# rpi-hxb-shield.net
KiCad netlist of a schematic drawn in EAGLE
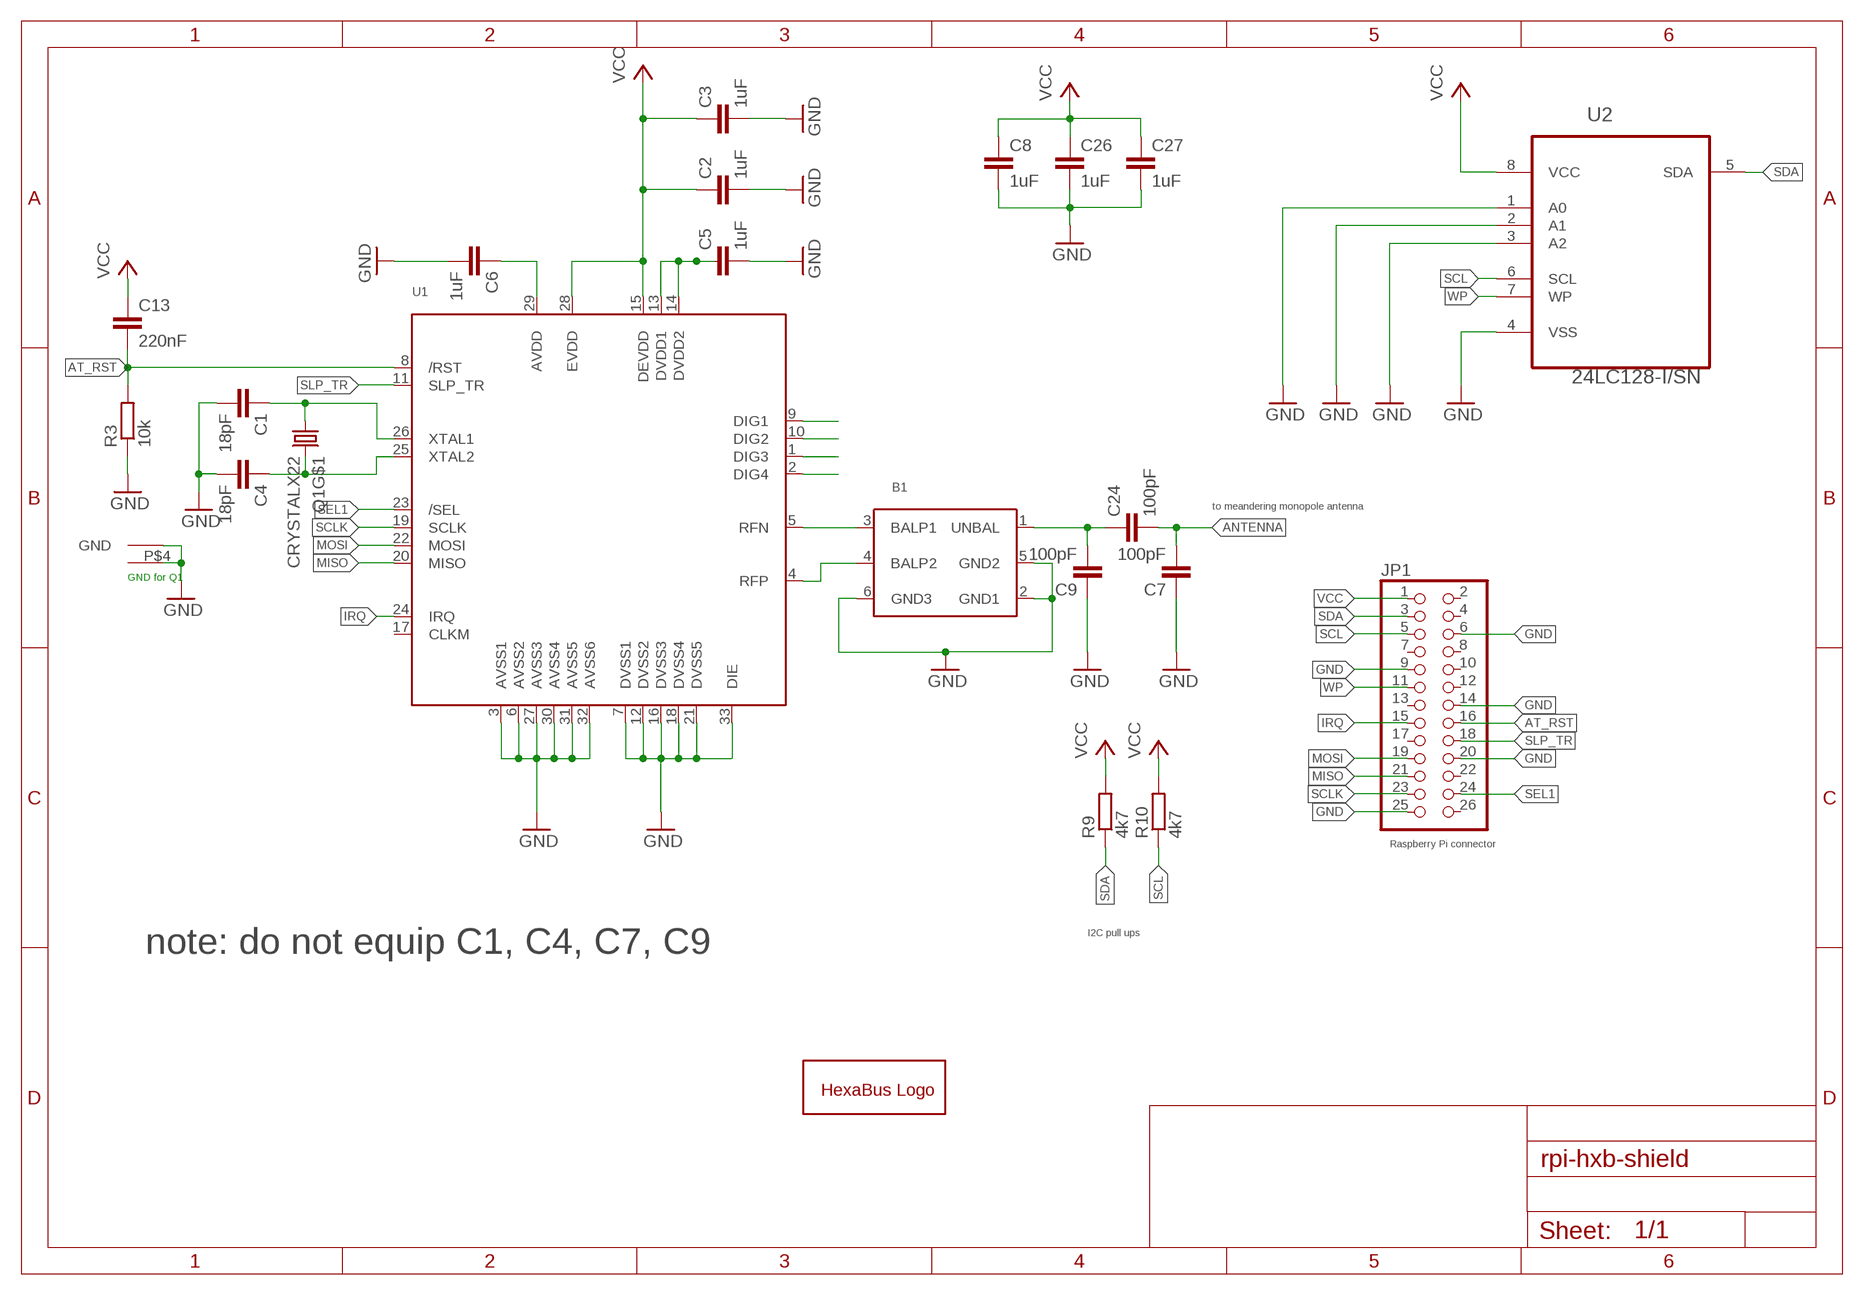
[diagram p0: schematic, sheet 1]

(export (version "E")
  (design (tool "Eeschema 10.0.6"))
  (components
    (comp (ref "B1")
      (value "BALUN+LP")
      (footprint "eagle-import:BALUN0805")
      (libsource (lib "eagle-import") (part "BALUN+LP"))
    )
    (comp (ref "C1")
      (value "18pF")
      (footprint "eagle-import:C0402K")
      (libsource (lib "eagle-import") (part "C-EUC0402K"))
    )
    (comp (ref "C2")
      (value "1uF")
      (footprint "eagle-import:C0402K")
      (libsource (lib "eagle-import") (part "C-EUC0402K"))
    )
    (comp (ref "C3")
      (value "1uF")
      (footprint "eagle-import:C0402K")
      (libsource (lib "eagle-import") (part "C-EUC0402K"))
    )
    (comp (ref "C4")
      (value "18pF")
      (footprint "eagle-import:C0402K")
      (libsource (lib "eagle-import") (part "C-EUC0402K"))
    )
    (comp (ref "C5")
      (value "1uF")
      (footprint "eagle-import:C0402K")
      (libsource (lib "eagle-import") (part "C-EUC0402K"))
    )
    (comp (ref "C6")
      (value "1uF")
      (footprint "eagle-import:C0402K")
      (libsource (lib "eagle-import") (part "C-EUC0402K"))
    )
    (comp (ref "C7")
      (value "100pF")
      (footprint "eagle-import:C0402K")
      (libsource (lib "eagle-import") (part "C-EUC0402K"))
    )
    (comp (ref "C8")
      (value "1uF")
      (footprint "eagle-import:C0402K")
      (libsource (lib "eagle-import") (part "C-EUC0402K"))
    )
    (comp (ref "C9")
      (value "100pF")
      (footprint "eagle-import:C0402K")
      (libsource (lib "eagle-import") (part "C-EUC0402K"))
    )
    (comp (ref "C13")
      (value "220nF")
      (footprint "eagle-import:C0402K")
      (libsource (lib "eagle-import") (part "C-EUC0402K"))
    )
    (comp (ref "C24")
      (value "100pF")
      (footprint "eagle-import:C0402K")
      (libsource (lib "eagle-import") (part "C-EUC0402K"))
    )
    (comp (ref "C26")
      (value "1uF")
      (footprint "eagle-import:C0402K")
      (libsource (lib "eagle-import") (part "C-EUC0402K"))
    )
    (comp (ref "C27")
      (value "1uF")
      (footprint "eagle-import:C0402K")
      (libsource (lib "eagle-import") (part "C-EUC0402K"))
    )
    (comp (ref "JP1")
      (value "PINHD-2X13")
      (footprint "eagle-import:2X13")
      (libsource (lib "eagle-import") (part "PINHD-2X13"))
    )
    (comp (ref "Q1")
      (value "CRYSTALX22")
      (footprint "eagle-import:X22")
      (libsource (lib "eagle-import") (part "CRYSTALX22"))
    )
    (comp (ref "R3")
      (value "10k")
      (footprint "eagle-import:R0402")
      (libsource (lib "eagle-import") (part "R-EU_R0402"))
    )
    (comp (ref "R9")
      (value "4k7")
      (footprint "eagle-import:R0402")
      (libsource (lib "eagle-import") (part "R-EU_R0402"))
    )
    (comp (ref "R10")
      (value "4k7")
      (footprint "eagle-import:R0402")
      (libsource (lib "eagle-import") (part "R-EU_R0402"))
    )
    (comp (ref "U$1")
      (value "HEXAKRAKE")
      (footprint "eagle-import:HEXAKRAKE")
      (libsource (lib "eagle-import") (part "HEXAKRAKE"))
    )
    (comp (ref "U1")
      (value "AT86RF212")
      (footprint "eagle-import:32QN2")
      (libsource (lib "eagle-import") (part "AT86RF212"))
    )
    (comp (ref "U2")
      (value "24LC128-I/SN")
      (footprint "eagle-import:SOIC127P600X175-8N")
      (libsource (lib "eagle-import") (part "24LC128-I/SN"))
    )
  )
  (nets
    (net (code "1") (name "ANTENNA") (class "Default")
      (node (ref "C24") (pin "2") (pinfunction "2_2") (pintype "passive"))
      (node (ref "C7") (pin "2") (pinfunction "2_2") (pintype "passive"))
    )
    (net (code "2") (name "AT_RST") (class "Default")
      (node (ref "C13") (pin "2") (pinfunction "2_2") (pintype "passive"))
      (node (ref "JP1") (pin "16") (pinfunction "16_16") (pintype "passive"))
      (node (ref "R3") (pin "2") (pinfunction "2_2") (pintype "passive"))
      (node (ref "U1") (pin "8") (pinfunction "/RST_8") (pintype "bidirectional"))
    )
    (net (code "3") (name "GND") (class "Default")
      (node (ref "B1") (pin "2") (pinfunction "GND1_2") (pintype "bidirectional"))
      (node (ref "B1") (pin "5") (pinfunction "GND2_5") (pintype "bidirectional"))
      (node (ref "B1") (pin "6") (pinfunction "GND3_6") (pintype "bidirectional"))
      (node (ref "C1") (pin "2") (pinfunction "2_2") (pintype "passive"))
      (node (ref "C2") (pin "2") (pinfunction "2_2") (pintype "passive"))
      (node (ref "C26") (pin "2") (pinfunction "2_2") (pintype "passive"))
      (node (ref "C27") (pin "2") (pinfunction "2_2") (pintype "passive"))
      (node (ref "C3") (pin "2") (pinfunction "2_2") (pintype "passive"))
      (node (ref "C4") (pin "2") (pinfunction "2_2") (pintype "passive"))
      (node (ref "C5") (pin "2") (pinfunction "2_2") (pintype "passive"))
      (node (ref "C6") (pin "2") (pinfunction "2_2") (pintype "passive"))
      (node (ref "C7") (pin "1") (pinfunction "1_1") (pintype "passive"))
      (node (ref "C8") (pin "2") (pinfunction "2_2") (pintype "passive"))
      (node (ref "C9") (pin "1") (pinfunction "1_1") (pintype "passive"))
      (node (ref "JP1") (pin "14") (pinfunction "14_14") (pintype "passive"))
      (node (ref "JP1") (pin "20") (pinfunction "20_20") (pintype "passive"))
      (node (ref "JP1") (pin "25") (pinfunction "25_25") (pintype "passive"))
      (node (ref "JP1") (pin "6") (pinfunction "6_6") (pintype "passive"))
      (node (ref "JP1") (pin "9") (pinfunction "9_9") (pintype "passive"))
      (node (ref "Q1") (pin "P$2") (pinfunction "GND_P$2") (pintype "bidirectional"))
      (node (ref "Q1") (pin "P$4") (pinfunction "GND1_P$4") (pintype "bidirectional"))
      (node (ref "R3") (pin "1") (pinfunction "1_1") (pintype "passive"))
      (node (ref "U1") (pin "12") (pinfunction "DVSS2_12") (pintype "bidirectional"))
      (node (ref "U1") (pin "16") (pinfunction "DVSS3_16") (pintype "bidirectional"))
      (node (ref "U1") (pin "18") (pinfunction "DVSS4_18") (pintype "bidirectional"))
      (node (ref "U1") (pin "21") (pinfunction "DVSS5_21") (pintype "bidirectional"))
      (node (ref "U1") (pin "27") (pinfunction "AVSS3_27") (pintype "bidirectional"))
      (node (ref "U1") (pin "3") (pinfunction "AVSS1_3") (pintype "bidirectional"))
      (node (ref "U1") (pin "30") (pinfunction "AVSS4_30") (pintype "bidirectional"))
      (node (ref "U1") (pin "31") (pinfunction "AVSS5_31") (pintype "bidirectional"))
      (node (ref "U1") (pin "32") (pinfunction "AVSS6_32") (pintype "bidirectional"))
      (node (ref "U1") (pin "33") (pinfunction "DIE_33") (pintype "bidirectional"))
      (node (ref "U1") (pin "6") (pinfunction "AVSS2_6") (pintype "bidirectional"))
      (node (ref "U1") (pin "7") (pinfunction "DVSS1_7") (pintype "bidirectional"))
      (node (ref "U2") (pin "1") (pinfunction "A0_1") (pintype "input"))
      (node (ref "U2") (pin "2") (pinfunction "A1_2") (pintype "input"))
      (node (ref "U2") (pin "3") (pinfunction "A2_3") (pintype "input"))
      (node (ref "U2") (pin "4") (pinfunction "VSS_4") (pintype "passive"))
    )
    (net (code "4") (name "IRQ") (class "Default")
      (node (ref "JP1") (pin "15") (pinfunction "15_15") (pintype "passive"))
      (node (ref "U1") (pin "24") (pinfunction "IRQ_24") (pintype "bidirectional"))
    )
    (net (code "5") (name "MISO") (class "Default")
      (node (ref "JP1") (pin "21") (pinfunction "21_21") (pintype "passive"))
      (node (ref "U1") (pin "20") (pinfunction "MISO_20") (pintype "bidirectional"))
    )
    (net (code "6") (name "MOSI") (class "Default")
      (node (ref "JP1") (pin "19") (pinfunction "19_19") (pintype "passive"))
      (node (ref "U1") (pin "22") (pinfunction "MOSI_22") (pintype "bidirectional"))
    )
    (net (code "7") (name "Net-(B1-BALP1)") (class "Default")
      (node (ref "B1") (pin "3") (pinfunction "BALP1_3") (pintype "bidirectional"))
      (node (ref "U1") (pin "5") (pinfunction "RFN_5") (pintype "bidirectional"))
    )
    (net (code "8") (name "Net-(B1-BALP2)") (class "Default")
      (node (ref "B1") (pin "4") (pinfunction "BALP2_4") (pintype "bidirectional"))
      (node (ref "U1") (pin "4") (pinfunction "RFP_4") (pintype "bidirectional"))
    )
    (net (code "9") (name "Net-(B1-UNBAL)") (class "Default")
      (node (ref "B1") (pin "1") (pinfunction "UNBAL_1") (pintype "bidirectional"))
      (node (ref "C24") (pin "1") (pinfunction "1_1") (pintype "passive"))
      (node (ref "C9") (pin "2") (pinfunction "2_2") (pintype "passive"))
    )
    (net (code "10") (name "Net-(Q1A-1)") (class "Default")
      (node (ref "C1") (pin "1") (pinfunction "1_1") (pintype "passive"))
      (node (ref "Q1") (pin "P$1") (pinfunction "1_P$1") (pintype "passive"))
      (node (ref "U1") (pin "26") (pinfunction "XTAL1_26") (pintype "bidirectional"))
    )
    (net (code "11") (name "Net-(Q1A-2)") (class "Default")
      (node (ref "C4") (pin "1") (pinfunction "1_1") (pintype "passive"))
      (node (ref "Q1") (pin "P$3") (pinfunction "2_P$3") (pintype "passive"))
      (node (ref "U1") (pin "25") (pinfunction "XTAL2_25") (pintype "bidirectional"))
    )
    (net (code "12") (name "Net-(U1-AVDD)") (class "Default")
      (node (ref "C6") (pin "1") (pinfunction "1_1") (pintype "passive"))
      (node (ref "U1") (pin "29") (pinfunction "AVDD_29") (pintype "bidirectional"))
    )
    (net (code "13") (name "Net-(U1-DVDD1)") (class "Default")
      (node (ref "C5") (pin "1") (pinfunction "1_1") (pintype "passive"))
      (node (ref "U1") (pin "13") (pinfunction "DVDD1_13") (pintype "bidirectional"))
      (node (ref "U1") (pin "14") (pinfunction "DVDD2_14") (pintype "bidirectional"))
    )
    (net (code "14") (name "SCL") (class "Default")
      (node (ref "JP1") (pin "5") (pinfunction "5_5") (pintype "passive"))
      (node (ref "R10") (pin "1") (pinfunction "1_1") (pintype "passive"))
      (node (ref "U2") (pin "6") (pinfunction "SCL_6") (pintype "input"))
    )
    (net (code "15") (name "SCLK") (class "Default")
      (node (ref "JP1") (pin "23") (pinfunction "23_23") (pintype "passive"))
      (node (ref "U1") (pin "19") (pinfunction "SCLK_19") (pintype "bidirectional"))
    )
    (net (code "16") (name "SDA") (class "Default")
      (node (ref "JP1") (pin "3") (pinfunction "3_3") (pintype "passive"))
      (node (ref "R9") (pin "1") (pinfunction "1_1") (pintype "passive"))
      (node (ref "U2") (pin "5") (pinfunction "SDA_5") (pintype "bidirectional"))
    )
    (net (code "17") (name "SEL1") (class "Default")
      (node (ref "JP1") (pin "24") (pinfunction "24_24") (pintype "passive"))
      (node (ref "U1") (pin "23") (pinfunction "/SEL_23") (pintype "bidirectional"))
    )
    (net (code "18") (name "SLP_TR") (class "Default")
      (node (ref "JP1") (pin "18") (pinfunction "18_18") (pintype "passive"))
      (node (ref "U1") (pin "11") (pinfunction "SLP_TR_11") (pintype "bidirectional"))
    )
    (net (code "19") (name "VCC") (class "Default")
      (node (ref "C13") (pin "1") (pinfunction "1_1") (pintype "passive"))
      (node (ref "C2") (pin "1") (pinfunction "1_1") (pintype "passive"))
      (node (ref "C26") (pin "1") (pinfunction "1_1") (pintype "passive"))
      (node (ref "C27") (pin "1") (pinfunction "1_1") (pintype "passive"))
      (node (ref "C3") (pin "1") (pinfunction "1_1") (pintype "passive"))
      (node (ref "C8") (pin "1") (pinfunction "1_1") (pintype "passive"))
      (node (ref "JP1") (pin "1") (pinfunction "1_1") (pintype "passive"))
      (node (ref "R10") (pin "2") (pinfunction "2_2") (pintype "passive"))
      (node (ref "R9") (pin "2") (pinfunction "2_2") (pintype "passive"))
      (node (ref "U1") (pin "15") (pinfunction "DEVDD_15") (pintype "bidirectional"))
      (node (ref "U1") (pin "28") (pinfunction "EVDD_28") (pintype "bidirectional"))
      (node (ref "U2") (pin "8") (pinfunction "VCC_8") (pintype "power_in"))
    )
    (net (code "20") (name "WP") (class "Default")
      (node (ref "JP1") (pin "11") (pinfunction "11_11") (pintype "passive"))
      (node (ref "U2") (pin "7") (pinfunction "WP_7") (pintype "input"))
    )
    (net (code "21") (name "unconnected-(JP1-Pad2)") (class "Default")
      (node (ref "JP1") (pin "2") (pinfunction "2_2") (pintype "passive"))
    )
    (net (code "22") (name "unconnected-(JP1-Pad4)") (class "Default")
      (node (ref "JP1") (pin "4") (pinfunction "4_4") (pintype "passive"))
    )
    (net (code "23") (name "unconnected-(JP1-Pad7)") (class "Default")
      (node (ref "JP1") (pin "7") (pinfunction "7_7") (pintype "passive"))
    )
    (net (code "24") (name "unconnected-(JP1-Pad8)") (class "Default")
      (node (ref "JP1") (pin "8") (pinfunction "8_8") (pintype "passive"))
    )
    (net (code "25") (name "unconnected-(JP1-Pad10)") (class "Default")
      (node (ref "JP1") (pin "10") (pinfunction "10_10") (pintype "passive"))
    )
    (net (code "26") (name "unconnected-(JP1-Pad12)") (class "Default")
      (node (ref "JP1") (pin "12") (pinfunction "12_12") (pintype "passive"))
    )
    (net (code "27") (name "unconnected-(JP1-Pad13)") (class "Default")
      (node (ref "JP1") (pin "13") (pinfunction "13_13") (pintype "passive"))
    )
    (net (code "28") (name "unconnected-(JP1-Pad17)") (class "Default")
      (node (ref "JP1") (pin "17") (pinfunction "17_17") (pintype "passive"))
    )
    (net (code "29") (name "unconnected-(JP1-Pad22)") (class "Default")
      (node (ref "JP1") (pin "22") (pinfunction "22_22") (pintype "passive"))
    )
    (net (code "30") (name "unconnected-(JP1-Pad26)") (class "Default")
      (node (ref "JP1") (pin "26") (pinfunction "26_26") (pintype "passive"))
    )
    (net (code "31") (name "unconnected-(U1-CLKM-Pad17)") (class "Default")
      (node (ref "U1") (pin "17") (pinfunction "CLKM_17") (pintype "bidirectional"))
    )
    (net (code "32") (name "unconnected-(U1-DIG1-Pad9)") (class "Default")
      (node (ref "U1") (pin "9") (pinfunction "DIG1_9") (pintype "bidirectional"))
    )
    (net (code "33") (name "unconnected-(U1-DIG2-Pad10)") (class "Default")
      (node (ref "U1") (pin "10") (pinfunction "DIG2_10") (pintype "bidirectional"))
    )
    (net (code "34") (name "unconnected-(U1-DIG3-Pad1)") (class "Default")
      (node (ref "U1") (pin "1") (pinfunction "DIG3_1") (pintype "bidirectional"))
    )
    (net (code "35") (name "unconnected-(U1-DIG4-Pad2)") (class "Default")
      (node (ref "U1") (pin "2") (pinfunction "DIG4_2") (pintype "bidirectional"))
    )
  )
)
